# DDR3_ZET6_OLD.net
KiCad netlist of a schematic drawn in Altium Designer
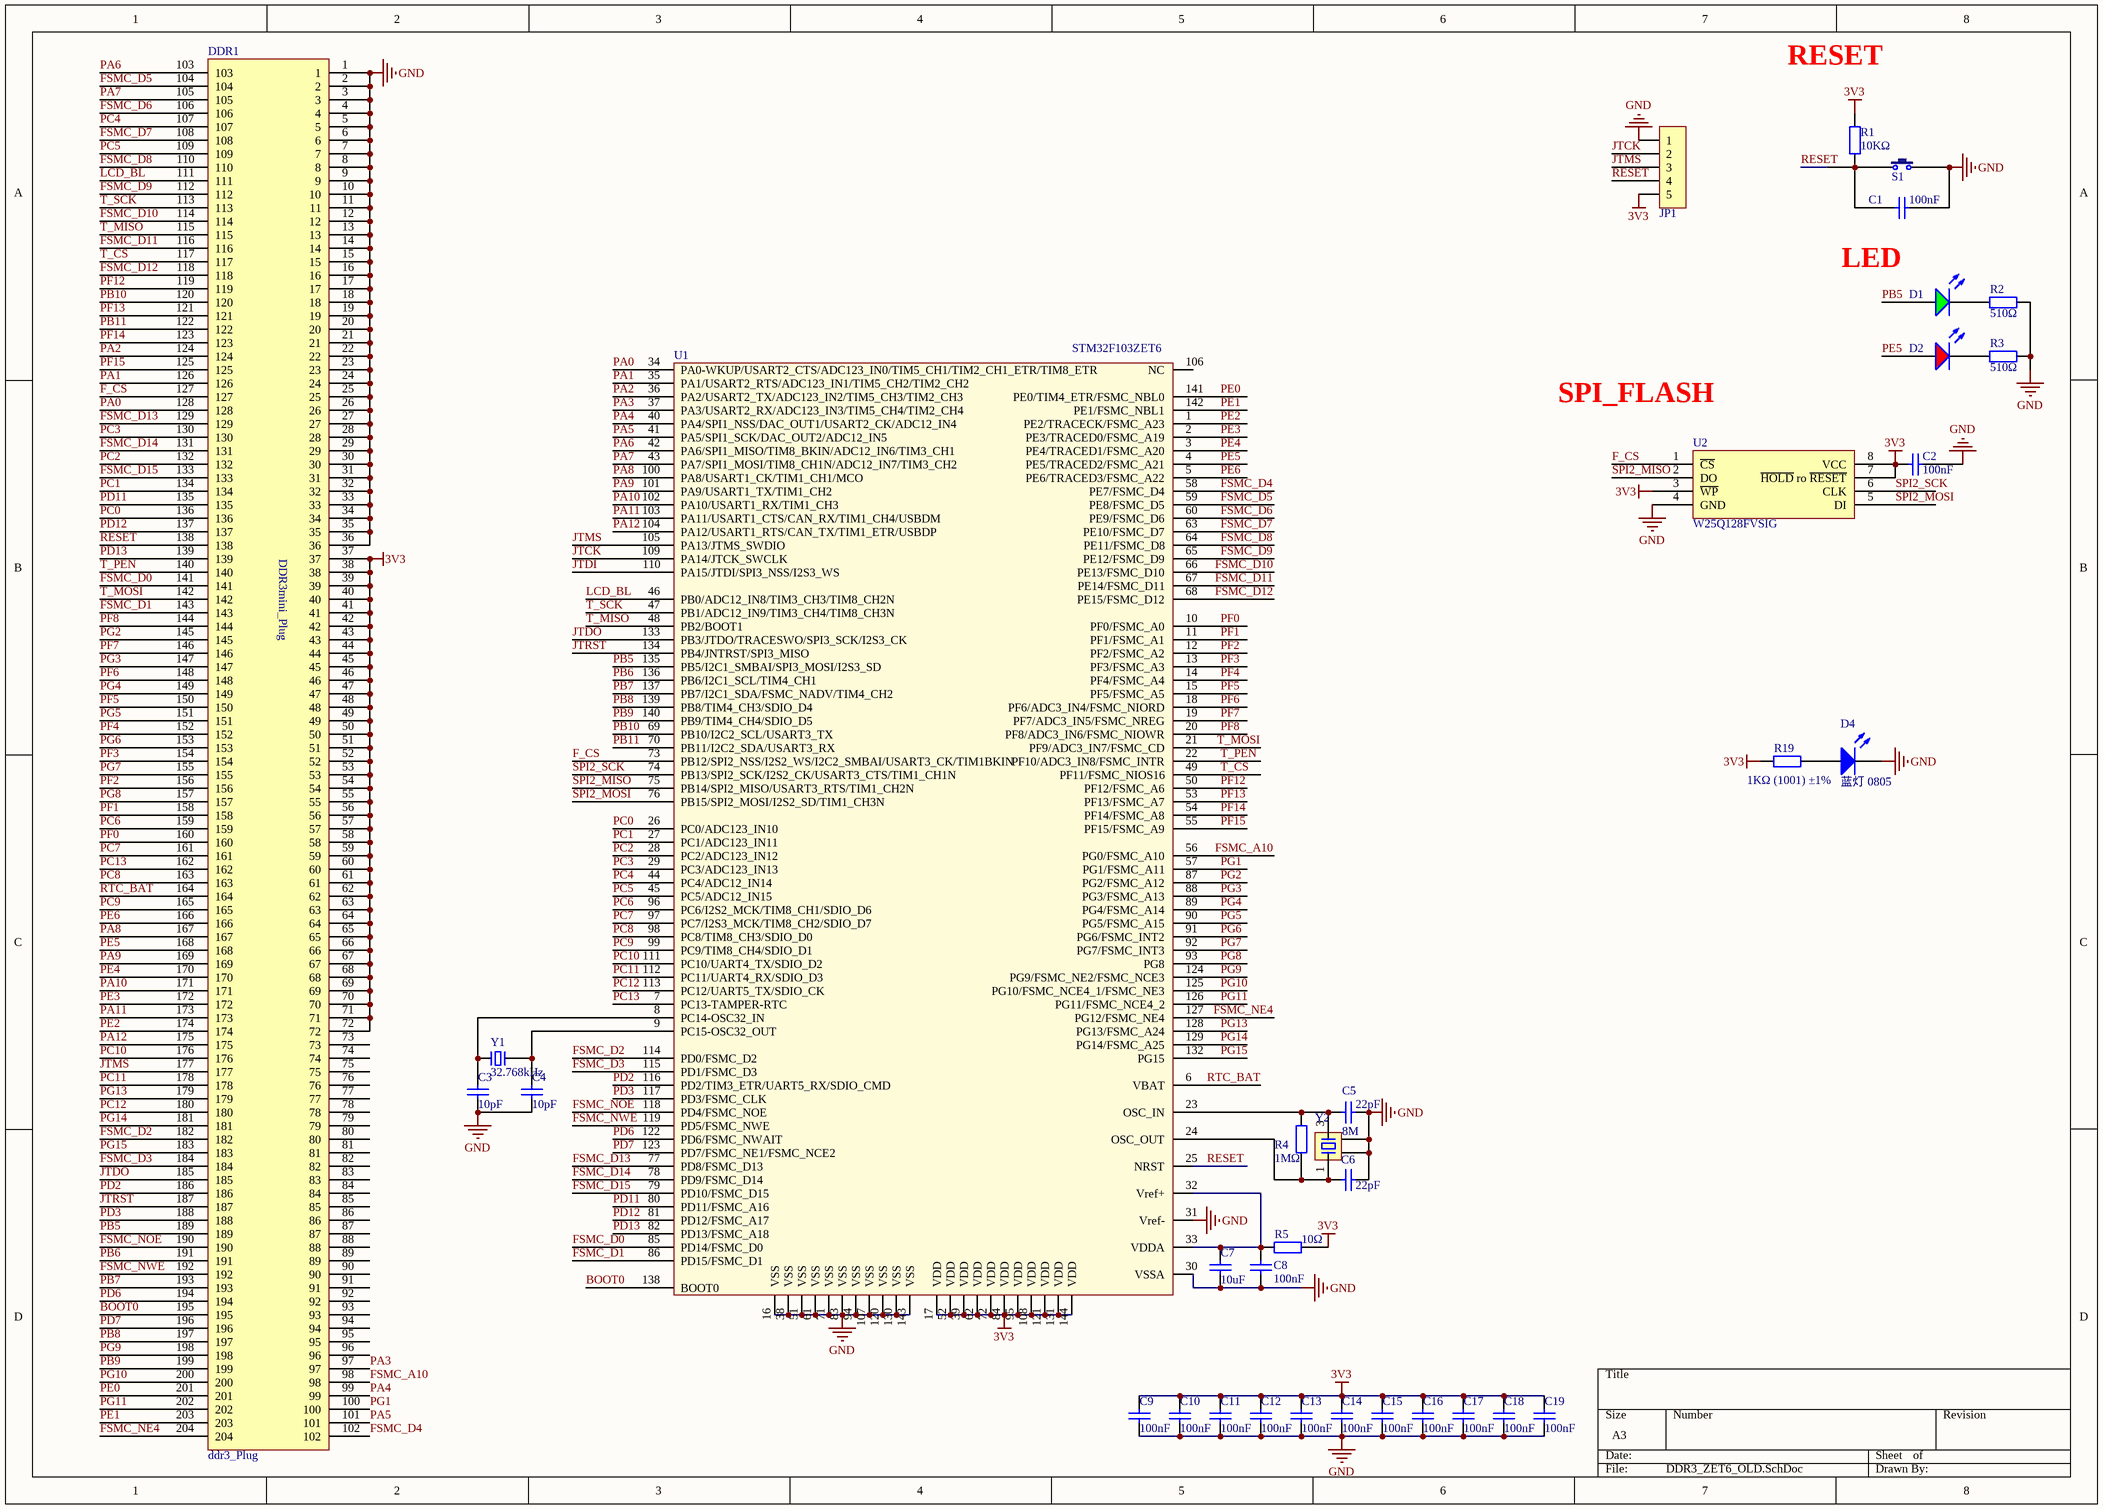
[diagram p0: DDR3_ZET6_OLD.SchDoc]

(export (version "E")
  (design (tool "Eeschema 10.0.6"))
  (components
    (comp (ref "C1")
      (value "100nF")
      (footprint "LC-0805_C")
      (description "贴片电容")
      (libsource (lib "Miscellaneous Devices LC") (part "0805 100nF(104) 10% 50V"))
    )
    (comp (ref "C2")
      (value "100nF")
      (footprint "LC-0805_C")
      (description "贴片电容")
      (libsource (lib "Miscellaneous Devices LC") (part "0805 100nF(104) 10% 50V"))
    )
    (comp (ref "C3")
      (value "10pF")
      (footprint "LC-0805_C")
      (description "贴片电容")
      (libsource (lib "Miscellaneous Devices LC") (part "0805 10pF (100) 5% 50V"))
    )
    (comp (ref "C4")
      (value "10pF")
      (footprint "LC-0805_C")
      (description "贴片电容")
      (libsource (lib "Miscellaneous Devices LC") (part "0805 10pF (100) 5% 50V"))
    )
    (comp (ref "C5")
      (value "22pF")
      (footprint "LC-0805_C")
      (description "贴片电容")
      (libsource (lib "Miscellaneous Devices LC") (part "0805 22pF (220) 5% 50V"))
    )
    (comp (ref "C6")
      (value "22pF")
      (footprint "LC-0805_C")
      (description "贴片电容")
      (libsource (lib "Miscellaneous Devices LC") (part "0805 22pF (220) 5% 50V"))
    )
    (comp (ref "C7")
      (value "10uF")
      (footprint "LC-0805_C")
      (description "贴片电容")
      (libsource (lib "Miscellaneous Devices LC") (part "0805 10uF (106) 10% 25V"))
    )
    (comp (ref "C8")
      (value "100nF")
      (footprint "LC-0805_C")
      (description "贴片电容")
      (libsource (lib "Miscellaneous Devices LC") (part "0805 100nF(104) 10% 50V"))
    )
    (comp (ref "C9")
      (value "100nF")
      (footprint "LC-0805_C")
      (description "贴片电容")
      (libsource (lib "Miscellaneous Devices LC") (part "0805 100nF(104) 10% 50V"))
    )
    (comp (ref "C10")
      (value "100nF")
      (footprint "LC-0805_C")
      (description "贴片电容")
      (libsource (lib "Miscellaneous Devices LC") (part "0805 100nF(104) 10% 50V"))
    )
    (comp (ref "C11")
      (value "100nF")
      (footprint "LC-0805_C")
      (description "贴片电容")
      (libsource (lib "Miscellaneous Devices LC") (part "0805 100nF(104) 10% 50V"))
    )
    (comp (ref "C12")
      (value "100nF")
      (footprint "LC-0805_C")
      (description "贴片电容")
      (libsource (lib "Miscellaneous Devices LC") (part "0805 100nF(104) 10% 50V"))
    )
    (comp (ref "C13")
      (value "100nF")
      (footprint "LC-0805_C")
      (description "贴片电容")
      (libsource (lib "Miscellaneous Devices LC") (part "0805 100nF(104) 10% 50V"))
    )
    (comp (ref "C14")
      (value "100nF")
      (footprint "LC-0805_C")
      (description "贴片电容")
      (libsource (lib "Miscellaneous Devices LC") (part "0805 100nF(104) 10% 50V"))
    )
    (comp (ref "C15")
      (value "100nF")
      (footprint "LC-0805_C")
      (description "贴片电容")
      (libsource (lib "Miscellaneous Devices LC") (part "0805 100nF(104) 10% 50V"))
    )
    (comp (ref "C16")
      (value "100nF")
      (footprint "LC-0805_C")
      (description "贴片电容")
      (libsource (lib "Miscellaneous Devices LC") (part "0805 100nF(104) 10% 50V"))
    )
    (comp (ref "C17")
      (value "100nF")
      (footprint "LC-0805_C")
      (description "贴片电容")
      (libsource (lib "Miscellaneous Devices LC") (part "0805 100nF(104) 10% 50V"))
    )
    (comp (ref "C18")
      (value "100nF")
      (footprint "LC-0805_C")
      (description "贴片电容")
      (libsource (lib "Miscellaneous Devices LC") (part "0805 100nF(104) 10% 50V"))
    )
    (comp (ref "C19")
      (value "100nF")
      (footprint "LC-0805_C")
      (description "贴片电容")
      (libsource (lib "Miscellaneous Devices LC") (part "0805 100nF(104) 10% 50V"))
    )
    (comp (ref "D1")
      (value "翠绿 0805")
      (footprint "LC-0805_LED_S1")
      (description "发光二极管")
      (libsource (lib "Miscellaneous Devices LC") (part "0805 翠绿"))
    )
    (comp (ref "D2")
      (value "红灯 0805")
      (footprint "LC-0805_LED_S1")
      (description "发光二极管")
      (libsource (lib "Miscellaneous Devices LC") (part "0805 红灯"))
    )
    (comp (ref "D4")
      (value "蓝灯 0805")
      (footprint "LC-0805_LED_S1")
      (description "发光二极管")
      (libsource (lib "Miscellaneous Devices LC") (part "0805 蓝灯"))
    )
    (comp (ref "DDR1")
      (value "ddr3_Plug")
      (footprint "DDR3_PLUG_LTE")
      (libsource (lib "my_lib") (part "ddr3_Plug"))
    )
    (comp (ref "JP1")
      (value "HDR-1X5")
      (footprint "HDR-1X5")
      (description "5P接插件")
      (fields (field (name "版权归属") "黎明电子style"))
      (libsource (lib "接插件") (part "Header 5"))
    )
    (comp (ref "R1")
      (value "10KΩ")
      (footprint "LC-0805_R")
      (description "贴片电阻")
      (libsource (lib "Miscellaneous Devices LC") (part "0805 10KΩ (1002) 1%"))
    )
    (comp (ref "R2")
      (value "510Ω")
      (footprint "LC-0805_R")
      (description "贴片电阻")
      (libsource (lib "Miscellaneous Devices LC") (part "0805 510Ω (5100) 1%"))
    )
    (comp (ref "R3")
      (value "510Ω")
      (footprint "LC-0805_R")
      (description "贴片电阻")
      (libsource (lib "Miscellaneous Devices LC") (part "0805 510Ω (5100) 1%"))
    )
    (comp (ref "R4")
      (value "1MΩ")
      (footprint "LC-0805_R")
      (description "贴片电阻")
      (libsource (lib "Miscellaneous Devices LC") (part "0805 1MΩ (1004) 1%"))
    )
    (comp (ref "R5")
      (value "10Ω")
      (footprint "LC-0805_R")
      (description "贴片电阻")
      (libsource (lib "Miscellaneous Devices LC") (part "0805 10Ω (10R0) 1%"))
    )
    (comp (ref "R19")
      (value "1KΩ (1001) ±1%")
      (footprint "LC-0805_R")
      (description "贴片电阻")
      (libsource (lib "Miscellaneous Devices LC") (part "0805 1KΩ (1001) 1%"))
    )
    (comp (ref "S1")
      (value "RESET")
      (footprint "TSW SMD-3*6*2.5")
      (description "3x6轻触开关")
      (fields (field (name "版权归属") "黎明电子style"))
      (libsource (lib "按键-开关") (part "TSW 3x6"))
    )
    (comp (ref "U1")
      (value "STM32F103ZET6")
      (footprint "LC-LQFP-144_20x20x05P")
      (libsource (lib "WarShip V3 STM32103封装库") (part "STM32F103ZET6"))
    )
    (comp (ref "U2")
      (value "W25Q128FVSIG")
      (footprint "LC-SOIC-8_208mil")
      (description "Flash ROM")
      (libsource (lib "Miscellaneous Devices LC") (part "W25Q128FVSIG"))
    )
    (comp (ref "Y1")
      (value "32.768kHz")
      (footprint "XTAL-3215")
      (description "2脚晶振")
      (fields (field (name "版权归属") "黎明电子style"))
      (libsource (lib "保险丝-晶振") (part "XTAL-2"))
    )
    (comp (ref "Y2")
      (value "8M")
      (footprint "XTAL-3225")
      (description "4脚晶振")
      (fields (field (name "版权归属") "黎明电子style"))
      (libsource (lib "保险丝-晶振") (part "XTAL-4"))
    )
  )
  (nets
    (net (code "1") (name "/BOOT0") (class "Default")
      (node (ref "DDR1") (pin "195") (pinfunction "195_195") (pintype "passive"))
      (node (ref "U1") (pin "138") (pinfunction "BOOT0_138") (pintype "passive"))
    )
    (net (code "2") (name "/FSMC_A10") (class "Default")
      (node (ref "DDR1") (pin "98") (pinfunction "98_98") (pintype "passive"))
      (node (ref "U1") (pin "56") (pinfunction "PG0/FSMC_A10_56") (pintype "passive"))
    )
    (net (code "3") (name "/FSMC_D0") (class "Default")
      (node (ref "DDR1") (pin "141") (pinfunction "141_141") (pintype "passive"))
      (node (ref "U1") (pin "85") (pinfunction "PD14/FSMC_D0_85") (pintype "passive"))
    )
    (net (code "4") (name "/FSMC_D1") (class "Default")
      (node (ref "DDR1") (pin "143") (pinfunction "143_143") (pintype "passive"))
      (node (ref "U1") (pin "86") (pinfunction "PD15/FSMC_D1_86") (pintype "passive"))
    )
    (net (code "5") (name "/FSMC_D2") (class "Default")
      (node (ref "DDR1") (pin "182") (pinfunction "182_182") (pintype "passive"))
      (node (ref "U1") (pin "114") (pinfunction "PD0/FSMC_D2_114") (pintype "passive"))
    )
    (net (code "6") (name "/FSMC_D3") (class "Default")
      (node (ref "DDR1") (pin "184") (pinfunction "184_184") (pintype "passive"))
      (node (ref "U1") (pin "115") (pinfunction "PD1/FSMC_D3_115") (pintype "passive"))
    )
    (net (code "7") (name "/FSMC_D4") (class "Default")
      (node (ref "DDR1") (pin "102") (pinfunction "102_102") (pintype "passive"))
      (node (ref "U1") (pin "58") (pinfunction "PE7/FSMC_D4_58") (pintype "passive"))
    )
    (net (code "8") (name "/FSMC_D5") (class "Default")
      (node (ref "DDR1") (pin "104") (pinfunction "104_104") (pintype "passive"))
      (node (ref "U1") (pin "59") (pinfunction "PE8/FSMC_D5_59") (pintype "passive"))
    )
    (net (code "9") (name "/FSMC_D6") (class "Default")
      (node (ref "DDR1") (pin "106") (pinfunction "106_106") (pintype "passive"))
      (node (ref "U1") (pin "60") (pinfunction "PE9/FSMC_D6_60") (pintype "passive"))
    )
    (net (code "10") (name "/FSMC_D7") (class "Default")
      (node (ref "DDR1") (pin "108") (pinfunction "108_108") (pintype "passive"))
      (node (ref "U1") (pin "63") (pinfunction "PE10/FSMC_D7_63") (pintype "passive"))
    )
    (net (code "11") (name "/FSMC_D8") (class "Default")
      (node (ref "DDR1") (pin "110") (pinfunction "110_110") (pintype "passive"))
      (node (ref "U1") (pin "64") (pinfunction "PE11/FSMC_D8_64") (pintype "passive"))
    )
    (net (code "12") (name "/FSMC_D9") (class "Default")
      (node (ref "DDR1") (pin "112") (pinfunction "112_112") (pintype "passive"))
      (node (ref "U1") (pin "65") (pinfunction "PE12/FSMC_D9_65") (pintype "passive"))
    )
    (net (code "13") (name "/FSMC_D10") (class "Default")
      (node (ref "DDR1") (pin "114") (pinfunction "114_114") (pintype "passive"))
      (node (ref "U1") (pin "66") (pinfunction "PE13/FSMC_D10_66") (pintype "passive"))
    )
    (net (code "14") (name "/FSMC_D11") (class "Default")
      (node (ref "DDR1") (pin "116") (pinfunction "116_116") (pintype "passive"))
      (node (ref "U1") (pin "67") (pinfunction "PE14/FSMC_D11_67") (pintype "passive"))
    )
    (net (code "15") (name "/FSMC_D12") (class "Default")
      (node (ref "DDR1") (pin "118") (pinfunction "118_118") (pintype "passive"))
      (node (ref "U1") (pin "68") (pinfunction "PE15/FSMC_D12_68") (pintype "passive"))
    )
    (net (code "16") (name "/FSMC_D13") (class "Default")
      (node (ref "DDR1") (pin "129") (pinfunction "129_129") (pintype "passive"))
      (node (ref "U1") (pin "77") (pinfunction "PD8/FSMC_D13_77") (pintype "passive"))
    )
    (net (code "17") (name "/FSMC_D14") (class "Default")
      (node (ref "DDR1") (pin "131") (pinfunction "131_131") (pintype "passive"))
      (node (ref "U1") (pin "78") (pinfunction "PD9/FSMC_D14_78") (pintype "passive"))
    )
    (net (code "18") (name "/FSMC_D15") (class "Default")
      (node (ref "DDR1") (pin "133") (pinfunction "133_133") (pintype "passive"))
      (node (ref "U1") (pin "79") (pinfunction "PD10/FSMC_D15_79") (pintype "passive"))
    )
    (net (code "19") (name "/FSMC_NE4") (class "Default")
      (node (ref "DDR1") (pin "204") (pinfunction "204_204") (pintype "passive"))
      (node (ref "U1") (pin "127") (pinfunction "PG12/FSMC_NE4_127") (pintype "passive"))
    )
    (net (code "20") (name "/FSMC_NOE") (class "Default")
      (node (ref "DDR1") (pin "190") (pinfunction "190_190") (pintype "passive"))
      (node (ref "U1") (pin "118") (pinfunction "PD4/FSMC_NOE_118") (pintype "passive"))
    )
    (net (code "21") (name "/FSMC_NWE") (class "Default")
      (node (ref "DDR1") (pin "192") (pinfunction "192_192") (pintype "passive"))
      (node (ref "U1") (pin "119") (pinfunction "PD5/FSMC_NWE_119") (pintype "passive"))
    )
    (net (code "22") (name "/F_CS") (class "Default")
      (node (ref "DDR1") (pin "127") (pinfunction "127_127") (pintype "passive"))
      (node (ref "U1") (pin "73") (pinfunction "PB12/SPI2_NSS/I2S2_WS/I2C2_SMBAI/USART3_CK/TIM1BKIN_73") (pintype "passive"))
      (node (ref "U2") (pin "1") (pinfunction "~{CS}_1") (pintype "passive"))
    )
    (net (code "23") (name "/JTCK") (class "Default")
      (node (ref "JP1") (pin "2") (pinfunction "2_2") (pintype "passive"))
      (node (ref "U1") (pin "109") (pinfunction "PA14/JTCK_SWCLK_109") (pintype "passive"))
    )
    (net (code "24") (name "/JTDI") (class "Default")
      (node (ref "U1") (pin "110") (pinfunction "PA15/JTDI/SPI3_NSS/I2S3_WS_110") (pintype "passive"))
    )
    (net (code "25") (name "/JTDO") (class "Default")
      (node (ref "DDR1") (pin "185") (pinfunction "185_185") (pintype "passive"))
      (node (ref "U1") (pin "133") (pinfunction "PB3/JTDO/TRACESWO/SPI3_SCK/I2S3_CK_133") (pintype "passive"))
    )
    (net (code "26") (name "/JTMS") (class "Default")
      (node (ref "DDR1") (pin "177") (pinfunction "177_177") (pintype "passive"))
      (node (ref "JP1") (pin "3") (pinfunction "3_3") (pintype "passive"))
      (node (ref "U1") (pin "105") (pinfunction "PA13/JTMS_SWDIO_105") (pintype "passive"))
    )
    (net (code "27") (name "/JTRST") (class "Default")
      (node (ref "DDR1") (pin "187") (pinfunction "187_187") (pintype "passive"))
      (node (ref "U1") (pin "134") (pinfunction "PB4/JNTRST/SPI3_MISO_134") (pintype "passive"))
    )
    (net (code "28") (name "/LCD_BL") (class "Default")
      (node (ref "DDR1") (pin "111") (pinfunction "111_111") (pintype "passive"))
      (node (ref "U1") (pin "46") (pinfunction "PB0/ADC12_IN8/TIM3_CH3/TIM8_CH2N_46") (pintype "passive"))
    )
    (net (code "29") (name "/PA0") (class "Default")
      (node (ref "DDR1") (pin "128") (pinfunction "128_128") (pintype "passive"))
      (node (ref "U1") (pin "34") (pinfunction "PA0-WKUP/USART2_CTS/ADC123_IN0/TIM5_CH1/TIM2_CH1_ETR/TIM8_ETR_34") (pintype "passive"))
    )
    (net (code "30") (name "/PA1") (class "Default")
      (node (ref "DDR1") (pin "126") (pinfunction "126_126") (pintype "passive"))
      (node (ref "U1") (pin "35") (pinfunction "PA1/USART2_RTS/ADC123_IN1/TIM5_CH2/TIM2_CH2_35") (pintype "passive"))
    )
    (net (code "31") (name "/PA2") (class "Default")
      (node (ref "DDR1") (pin "124") (pinfunction "124_124") (pintype "passive"))
      (node (ref "U1") (pin "36") (pinfunction "PA2/USART2_TX/ADC123_IN2/TIM5_CH3/TIM2_CH3_36") (pintype "passive"))
    )
    (net (code "32") (name "/PA3") (class "Default")
      (node (ref "DDR1") (pin "97") (pinfunction "97_97") (pintype "passive"))
      (node (ref "U1") (pin "37") (pinfunction "PA3/USART2_RX/ADC123_IN3/TIM5_CH4/TIM2_CH4_37") (pintype "passive"))
    )
    (net (code "33") (name "/PA4") (class "Default")
      (node (ref "DDR1") (pin "99") (pinfunction "99_99") (pintype "passive"))
      (node (ref "U1") (pin "40") (pinfunction "PA4/SPI1_NSS/DAC_OUT1/USART2_CK/ADC12_IN4_40") (pintype "passive"))
    )
    (net (code "34") (name "/PA5") (class "Default")
      (node (ref "DDR1") (pin "101") (pinfunction "101_101") (pintype "passive"))
      (node (ref "U1") (pin "41") (pinfunction "PA5/SPI1_SCK/DAC_OUT2/ADC12_IN5_41") (pintype "passive"))
    )
    (net (code "35") (name "/PA6") (class "Default")
      (node (ref "DDR1") (pin "103") (pinfunction "103_103") (pintype "passive"))
      (node (ref "U1") (pin "42") (pinfunction "PA6/SPI1_MISO/TIM8_BKIN/ADC12_IN6/TIM3_CH1_42") (pintype "passive"))
    )
    (net (code "36") (name "/PA7") (class "Default")
      (node (ref "DDR1") (pin "105") (pinfunction "105_105") (pintype "passive"))
      (node (ref "U1") (pin "43") (pinfunction "PA7/SPI1_MOSI/TIM8_CH1N/ADC12_IN7/TIM3_CH2_43") (pintype "passive"))
    )
    (net (code "37") (name "/PA8") (class "Default")
      (node (ref "DDR1") (pin "167") (pinfunction "167_167") (pintype "passive"))
      (node (ref "U1") (pin "100") (pinfunction "PA8/USART1_CK/TIM1_CH1/MCO_100") (pintype "passive"))
    )
    (net (code "38") (name "/PA9") (class "Default")
      (node (ref "DDR1") (pin "169") (pinfunction "169_169") (pintype "passive"))
      (node (ref "U1") (pin "101") (pinfunction "PA9/USART1_TX/TIM1_CH2_101") (pintype "passive"))
    )
    (net (code "39") (name "/PA10") (class "Default")
      (node (ref "DDR1") (pin "171") (pinfunction "171_171") (pintype "passive"))
      (node (ref "U1") (pin "102") (pinfunction "PA10/USART1_RX/TIM1_CH3_102") (pintype "passive"))
    )
    (net (code "40") (name "/PA11") (class "Default")
      (node (ref "DDR1") (pin "173") (pinfunction "173_173") (pintype "passive"))
      (node (ref "U1") (pin "103") (pinfunction "PA11/USART1_CTS/CAN_RX/TIM1_CH4/USBDM_103") (pintype "passive"))
    )
    (net (code "41") (name "/PA12") (class "Default")
      (node (ref "DDR1") (pin "175") (pinfunction "175_175") (pintype "passive"))
      (node (ref "U1") (pin "104") (pinfunction "PA12/USART1_RTS/CAN_TX/TIM1_ETR/USBDP_104") (pintype "passive"))
    )
    (net (code "42") (name "/PB5") (class "Default")
      (node (ref "D1") (pin "A") (pinfunction "A_A") (pintype "passive"))
      (node (ref "DDR1") (pin "189") (pinfunction "189_189") (pintype "passive"))
      (node (ref "U1") (pin "135") (pinfunction "PB5/I2C1_SMBAI/SPI3_MOSI/I2S3_SD_135") (pintype "passive"))
    )
    (net (code "43") (name "/PB6") (class "Default")
      (node (ref "DDR1") (pin "191") (pinfunction "191_191") (pintype "passive"))
      (node (ref "U1") (pin "136") (pinfunction "PB6/I2C1_SCL/TIM4_CH1_136") (pintype "passive"))
    )
    (net (code "44") (name "/PB7") (class "Default")
      (node (ref "DDR1") (pin "193") (pinfunction "193_193") (pintype "passive"))
      (node (ref "U1") (pin "137") (pinfunction "PB7/I2C1_SDA/FSMC_NADV/TIM4_CH2_137") (pintype "passive"))
    )
    (net (code "45") (name "/PB8") (class "Default")
      (node (ref "DDR1") (pin "197") (pinfunction "197_197") (pintype "passive"))
      (node (ref "U1") (pin "139") (pinfunction "PB8/TIM4_CH3/SDIO_D4_139") (pintype "passive"))
    )
    (net (code "46") (name "/PB9") (class "Default")
      (node (ref "DDR1") (pin "199") (pinfunction "199_199") (pintype "passive"))
      (node (ref "U1") (pin "140") (pinfunction "PB9/TIM4_CH4/SDIO_D5_140") (pintype "passive"))
    )
    (net (code "47") (name "/PB10") (class "Default")
      (node (ref "DDR1") (pin "120") (pinfunction "120_120") (pintype "passive"))
      (node (ref "U1") (pin "69") (pinfunction "PB10/I2C2_SCL/USART3_TX_69") (pintype "passive"))
    )
    (net (code "48") (name "/PB11") (class "Default")
      (node (ref "DDR1") (pin "122") (pinfunction "122_122") (pintype "passive"))
      (node (ref "U1") (pin "70") (pinfunction "PB11/I2C2_SDA/USART3_RX_70") (pintype "passive"))
    )
    (net (code "49") (name "/PC0") (class "Default")
      (node (ref "DDR1") (pin "136") (pinfunction "136_136") (pintype "passive"))
      (node (ref "U1") (pin "26") (pinfunction "PC0/ADC123_IN10_26") (pintype "passive"))
    )
    (net (code "50") (name "/PC1") (class "Default")
      (node (ref "DDR1") (pin "134") (pinfunction "134_134") (pintype "passive"))
      (node (ref "U1") (pin "27") (pinfunction "PC1/ADC123_IN11_27") (pintype "passive"))
    )
    (net (code "51") (name "/PC2") (class "Default")
      (node (ref "DDR1") (pin "132") (pinfunction "132_132") (pintype "passive"))
      (node (ref "U1") (pin "28") (pinfunction "PC2/ADC123_IN12_28") (pintype "passive"))
    )
    (net (code "52") (name "/PC3") (class "Default")
      (node (ref "DDR1") (pin "130") (pinfunction "130_130") (pintype "passive"))
      (node (ref "U1") (pin "29") (pinfunction "PC3/ADC123_IN13_29") (pintype "passive"))
    )
    (net (code "53") (name "/PC4") (class "Default")
      (node (ref "DDR1") (pin "107") (pinfunction "107_107") (pintype "passive"))
      (node (ref "U1") (pin "44") (pinfunction "PC4/ADC12_IN14_44") (pintype "passive"))
    )
    (net (code "54") (name "/PC5") (class "Default")
      (node (ref "DDR1") (pin "109") (pinfunction "109_109") (pintype "passive"))
      (node (ref "U1") (pin "45") (pinfunction "PC5/ADC12_IN15_45") (pintype "passive"))
    )
    (net (code "55") (name "/PC6") (class "Default")
      (node (ref "DDR1") (pin "159") (pinfunction "159_159") (pintype "passive"))
      (node (ref "U1") (pin "96") (pinfunction "PC6/I2S2_MCK/TIM8_CH1/SDIO_D6_96") (pintype "passive"))
    )
    (net (code "56") (name "/PC7") (class "Default")
      (node (ref "DDR1") (pin "161") (pinfunction "161_161") (pintype "passive"))
      (node (ref "U1") (pin "97") (pinfunction "PC7/I2S3_MCK/TIM8_CH2/SDIO_D7_97") (pintype "passive"))
    )
    (net (code "57") (name "/PC8") (class "Default")
      (node (ref "DDR1") (pin "163") (pinfunction "163_163") (pintype "passive"))
      (node (ref "U1") (pin "98") (pinfunction "PC8/TIM8_CH3/SDIO_D0_98") (pintype "passive"))
    )
    (net (code "58") (name "/PC9") (class "Default")
      (node (ref "DDR1") (pin "165") (pinfunction "165_165") (pintype "passive"))
      (node (ref "U1") (pin "99") (pinfunction "PC9/TIM8_CH4/SDIO_D1_99") (pintype "passive"))
    )
    (net (code "59") (name "/PC10") (class "Default")
      (node (ref "DDR1") (pin "176") (pinfunction "176_176") (pintype "passive"))
      (node (ref "U1") (pin "111") (pinfunction "PC10/UART4_TX/SDIO_D2_111") (pintype "passive"))
    )
    (net (code "60") (name "/PC11") (class "Default")
      (node (ref "DDR1") (pin "178") (pinfunction "178_178") (pintype "passive"))
      (node (ref "U1") (pin "112") (pinfunction "PC11/UART4_RX/SDIO_D3_112") (pintype "passive"))
    )
    (net (code "61") (name "/PC12") (class "Default")
      (node (ref "DDR1") (pin "180") (pinfunction "180_180") (pintype "passive"))
      (node (ref "U1") (pin "113") (pinfunction "PC12/UART5_TX/SDIO_CK_113") (pintype "passive"))
    )
    (net (code "62") (name "/PC13") (class "Default")
      (node (ref "DDR1") (pin "162") (pinfunction "162_162") (pintype "passive"))
      (node (ref "U1") (pin "7") (pinfunction "PC13-TAMPER-RTC_7") (pintype "passive"))
    )
    (net (code "63") (name "/PD2") (class "Default")
      (node (ref "DDR1") (pin "186") (pinfunction "186_186") (pintype "passive"))
      (node (ref "U1") (pin "116") (pinfunction "PD2/TIM3_ETR/UART5_RX/SDIO_CMD_116") (pintype "passive"))
    )
    (net (code "64") (name "/PD3") (class "Default")
      (node (ref "DDR1") (pin "188") (pinfunction "188_188") (pintype "passive"))
      (node (ref "U1") (pin "117") (pinfunction "PD3/FSMC_CLK_117") (pintype "passive"))
    )
    (net (code "65") (name "/PD6") (class "Default")
      (node (ref "DDR1") (pin "194") (pinfunction "194_194") (pintype "passive"))
      (node (ref "U1") (pin "122") (pinfunction "PD6/FSMC_NWAIT_122") (pintype "passive"))
    )
    (net (code "66") (name "/PD7") (class "Default")
      (node (ref "DDR1") (pin "196") (pinfunction "196_196") (pintype "passive"))
      (node (ref "U1") (pin "123") (pinfunction "PD7/FSMC_NE1/FSMC_NCE2_123") (pintype "passive"))
    )
    (net (code "67") (name "/PD11") (class "Default")
      (node (ref "DDR1") (pin "135") (pinfunction "135_135") (pintype "passive"))
      (node (ref "U1") (pin "80") (pinfunction "PD11/FSMC_A16_80") (pintype "passive"))
    )
    (net (code "68") (name "/PD12") (class "Default")
      (node (ref "DDR1") (pin "137") (pinfunction "137_137") (pintype "passive"))
      (node (ref "U1") (pin "81") (pinfunction "PD12/FSMC_A17_81") (pintype "passive"))
    )
    (net (code "69") (name "/PD13") (class "Default")
      (node (ref "DDR1") (pin "139") (pinfunction "139_139") (pintype "passive"))
      (node (ref "U1") (pin "82") (pinfunction "PD13/FSMC_A18_82") (pintype "passive"))
    )
    (net (code "70") (name "/PE0") (class "Default")
      (node (ref "DDR1") (pin "201") (pinfunction "201_201") (pintype "passive"))
      (node (ref "U1") (pin "141") (pinfunction "PE0/TIM4_ETR/FSMC_NBL0_141") (pintype "passive"))
    )
    (net (code "71") (name "/PE1") (class "Default")
      (node (ref "DDR1") (pin "203") (pinfunction "203_203") (pintype "passive"))
      (node (ref "U1") (pin "142") (pinfunction "PE1/FSMC_NBL1_142") (pintype "passive"))
    )
    (net (code "72") (name "/PE2") (class "Default")
      (node (ref "DDR1") (pin "174") (pinfunction "174_174") (pintype "passive"))
      (node (ref "U1") (pin "1") (pinfunction "PE2/TRACECK/FSMC_A23_1") (pintype "passive"))
    )
    (net (code "73") (name "/PE3") (class "Default")
      (node (ref "DDR1") (pin "172") (pinfunction "172_172") (pintype "passive"))
      (node (ref "U1") (pin "2") (pinfunction "PE3/TRACED0/FSMC_A19_2") (pintype "passive"))
    )
    (net (code "74") (name "/PE4") (class "Default")
      (node (ref "DDR1") (pin "170") (pinfunction "170_170") (pintype "passive"))
      (node (ref "U1") (pin "3") (pinfunction "PE4/TRACED1/FSMC_A20_3") (pintype "passive"))
    )
    (net (code "75") (name "/PE5") (class "Default")
      (node (ref "D2") (pin "A") (pinfunction "A_A") (pintype "passive"))
      (node (ref "DDR1") (pin "168") (pinfunction "168_168") (pintype "passive"))
      (node (ref "U1") (pin "4") (pinfunction "PE5/TRACED2/FSMC_A21_4") (pintype "passive"))
    )
    (net (code "76") (name "/PE6") (class "Default")
      (node (ref "DDR1") (pin "166") (pinfunction "166_166") (pintype "passive"))
      (node (ref "U1") (pin "5") (pinfunction "PE6/TRACED3/FSMC_A22_5") (pintype "passive"))
    )
    (net (code "77") (name "/PF0") (class "Default")
      (node (ref "DDR1") (pin "160") (pinfunction "160_160") (pintype "passive"))
      (node (ref "U1") (pin "10") (pinfunction "PF0/FSMC_A0_10") (pintype "passive"))
    )
    (net (code "78") (name "/PF1") (class "Default")
      (node (ref "DDR1") (pin "158") (pinfunction "158_158") (pintype "passive"))
      (node (ref "U1") (pin "11") (pinfunction "PF1/FSMC_A1_11") (pintype "passive"))
    )
    (net (code "79") (name "/PF2") (class "Default")
      (node (ref "DDR1") (pin "156") (pinfunction "156_156") (pintype "passive"))
      (node (ref "U1") (pin "12") (pinfunction "PF2/FSMC_A2_12") (pintype "passive"))
    )
    (net (code "80") (name "/PF3") (class "Default")
      (node (ref "DDR1") (pin "154") (pinfunction "154_154") (pintype "passive"))
      (node (ref "U1") (pin "13") (pinfunction "PF3/FSMC_A3_13") (pintype "passive"))
    )
    (net (code "81") (name "/PF4") (class "Default")
      (node (ref "DDR1") (pin "152") (pinfunction "152_152") (pintype "passive"))
      (node (ref "U1") (pin "14") (pinfunction "PF4/FSMC_A4_14") (pintype "passive"))
    )
    (net (code "82") (name "/PF5") (class "Default")
      (node (ref "DDR1") (pin "150") (pinfunction "150_150") (pintype "passive"))
      (node (ref "U1") (pin "15") (pinfunction "PF5/FSMC_A5_15") (pintype "passive"))
    )
    (net (code "83") (name "/PF6") (class "Default")
      (node (ref "DDR1") (pin "148") (pinfunction "148_148") (pintype "passive"))
      (node (ref "U1") (pin "18") (pinfunction "PF6/ADC3_IN4/FSMC_NIORD_18") (pintype "passive"))
    )
    (net (code "84") (name "/PF7") (class "Default")
      (node (ref "DDR1") (pin "146") (pinfunction "146_146") (pintype "passive"))
      (node (ref "U1") (pin "19") (pinfunction "PF7/ADC3_IN5/FSMC_NREG_19") (pintype "passive"))
    )
    (net (code "85") (name "/PF8") (class "Default")
      (node (ref "DDR1") (pin "144") (pinfunction "144_144") (pintype "passive"))
      (node (ref "U1") (pin "20") (pinfunction "PF8/ADC3_IN6/FSMC_NIOWR_20") (pintype "passive"))
    )
    (net (code "86") (name "/PF12") (class "Default")
      (node (ref "DDR1") (pin "119") (pinfunction "119_119") (pintype "passive"))
      (node (ref "U1") (pin "50") (pinfunction "PF12/FSMC_A6_50") (pintype "passive"))
    )
    (net (code "87") (name "/PF13") (class "Default")
      (node (ref "DDR1") (pin "121") (pinfunction "121_121") (pintype "passive"))
      (node (ref "U1") (pin "53") (pinfunction "PF13/FSMC_A7_53") (pintype "passive"))
    )
    (net (code "88") (name "/PF14") (class "Default")
      (node (ref "DDR1") (pin "123") (pinfunction "123_123") (pintype "passive"))
      (node (ref "U1") (pin "54") (pinfunction "PF14/FSMC_A8_54") (pintype "passive"))
    )
    (net (code "89") (name "/PF15") (class "Default")
      (node (ref "DDR1") (pin "125") (pinfunction "125_125") (pintype "passive"))
      (node (ref "U1") (pin "55") (pinfunction "PF15/FSMC_A9_55") (pintype "passive"))
    )
    (net (code "90") (name "/PG1") (class "Default")
      (node (ref "DDR1") (pin "100") (pinfunction "100_100") (pintype "passive"))
      (node (ref "U1") (pin "57") (pinfunction "PG1/FSMC_A11_57") (pintype "passive"))
    )
    (net (code "91") (name "/PG2") (class "Default")
      (node (ref "DDR1") (pin "145") (pinfunction "145_145") (pintype "passive"))
      (node (ref "U1") (pin "87") (pinfunction "PG2/FSMC_A12_87") (pintype "passive"))
    )
    (net (code "92") (name "/PG3") (class "Default")
      (node (ref "DDR1") (pin "147") (pinfunction "147_147") (pintype "passive"))
      (node (ref "U1") (pin "88") (pinfunction "PG3/FSMC_A13_88") (pintype "passive"))
    )
    (net (code "93") (name "/PG4") (class "Default")
      (node (ref "DDR1") (pin "149") (pinfunction "149_149") (pintype "passive"))
      (node (ref "U1") (pin "89") (pinfunction "PG4/FSMC_A14_89") (pintype "passive"))
    )
    (net (code "94") (name "/PG5") (class "Default")
      (node (ref "DDR1") (pin "151") (pinfunction "151_151") (pintype "passive"))
      (node (ref "U1") (pin "90") (pinfunction "PG5/FSMC_A15_90") (pintype "passive"))
    )
    (net (code "95") (name "/PG6") (class "Default")
      (node (ref "DDR1") (pin "153") (pinfunction "153_153") (pintype "passive"))
      (node (ref "U1") (pin "91") (pinfunction "PG6/FSMC_INT2_91") (pintype "passive"))
    )
    (net (code "96") (name "/PG7") (class "Default")
      (node (ref "DDR1") (pin "155") (pinfunction "155_155") (pintype "passive"))
      (node (ref "U1") (pin "92") (pinfunction "PG7/FSMC_INT3_92") (pintype "passive"))
    )
    (net (code "97") (name "/PG8") (class "Default")
      (node (ref "DDR1") (pin "157") (pinfunction "157_157") (pintype "passive"))
      (node (ref "U1") (pin "93") (pinfunction "PG8_93") (pintype "passive"))
    )
    (net (code "98") (name "/PG9") (class "Default")
      (node (ref "DDR1") (pin "198") (pinfunction "198_198") (pintype "passive"))
      (node (ref "U1") (pin "124") (pinfunction "PG9/FSMC_NE2/FSMC_NCE3_124") (pintype "passive"))
    )
    (net (code "99") (name "/PG10") (class "Default")
      (node (ref "DDR1") (pin "200") (pinfunction "200_200") (pintype "passive"))
      (node (ref "U1") (pin "125") (pinfunction "PG10/FSMC_NCE4_1/FSMC_NE3_125") (pintype "passive"))
    )
    (net (code "100") (name "/PG11") (class "Default")
      (node (ref "DDR1") (pin "202") (pinfunction "202_202") (pintype "passive"))
      (node (ref "U1") (pin "126") (pinfunction "PG11/FSMC_NCE4_2_126") (pintype "passive"))
    )
    (net (code "101") (name "/PG13") (class "Default")
      (node (ref "DDR1") (pin "179") (pinfunction "179_179") (pintype "passive"))
      (node (ref "U1") (pin "128") (pinfunction "PG13/FSMC_A24_128") (pintype "passive"))
    )
    (net (code "102") (name "/PG14") (class "Default")
      (node (ref "DDR1") (pin "181") (pinfunction "181_181") (pintype "passive"))
      (node (ref "U1") (pin "129") (pinfunction "PG14/FSMC_A25_129") (pintype "passive"))
    )
    (net (code "103") (name "/PG15") (class "Default")
      (node (ref "DDR1") (pin "183") (pinfunction "183_183") (pintype "passive"))
      (node (ref "U1") (pin "132") (pinfunction "PG15_132") (pintype "passive"))
    )
    (net (code "104") (name "/RESET") (class "Default")
      (node (ref "C1") (pin "1") (pinfunction "1_1") (pintype "passive"))
      (node (ref "DDR1") (pin "138") (pinfunction "138_138") (pintype "passive"))
      (node (ref "JP1") (pin "4") (pinfunction "4_4") (pintype "passive"))
      (node (ref "R1") (pin "1") (pinfunction "1_1") (pintype "passive"))
      (node (ref "S1") (pin "1") (pinfunction "1_1") (pintype "passive"))
      (node (ref "U1") (pin "25") (pinfunction "NRST_25") (pintype "passive"))
    )
    (net (code "105") (name "/RTC_BAT") (class "Default")
      (node (ref "DDR1") (pin "164") (pinfunction "164_164") (pintype "passive"))
      (node (ref "U1") (pin "6") (pinfunction "VBAT_6") (pintype "passive"))
    )
    (net (code "106") (name "/SPI2_MISO") (class "Default")
      (node (ref "U1") (pin "75") (pinfunction "PB14/SPI2_MISO/USART3_RTS/TIM1_CH2N_75") (pintype "passive"))
      (node (ref "U2") (pin "2") (pinfunction "DO_2") (pintype "passive"))
    )
    (net (code "107") (name "/SPI2_MOSI") (class "Default")
      (node (ref "U1") (pin "76") (pinfunction "PB15/SPI2_MOSI/I2S2_SD/TIM1_CH3N_76") (pintype "passive"))
      (node (ref "U2") (pin "5") (pinfunction "DI_5") (pintype "passive"))
    )
    (net (code "108") (name "/SPI2_SCK") (class "Default")
      (node (ref "U1") (pin "74") (pinfunction "PB13/SPI2_SCK/I2S2_CK/USART3_CTS/TIM1_CH1N_74") (pintype "passive"))
      (node (ref "U2") (pin "6") (pinfunction "CLK_6") (pintype "passive"))
    )
    (net (code "109") (name "/T_CS") (class "Default")
      (node (ref "DDR1") (pin "117") (pinfunction "117_117") (pintype "passive"))
      (node (ref "U1") (pin "49") (pinfunction "PF11/FSMC_NIOS16_49") (pintype "passive"))
    )
    (net (code "110") (name "/T_MISO") (class "Default")
      (node (ref "DDR1") (pin "115") (pinfunction "115_115") (pintype "passive"))
      (node (ref "U1") (pin "48") (pinfunction "PB2/BOOT1_48") (pintype "passive"))
    )
    (net (code "111") (name "/T_MOSI") (class "Default")
      (node (ref "DDR1") (pin "142") (pinfunction "142_142") (pintype "passive"))
      (node (ref "U1") (pin "21") (pinfunction "PF9/ADC3_IN7/FSMC_CD_21") (pintype "passive"))
    )
    (net (code "112") (name "/T_PEN") (class "Default")
      (node (ref "DDR1") (pin "140") (pinfunction "140_140") (pintype "passive"))
      (node (ref "U1") (pin "22") (pinfunction "PF10/ADC3_IN8/FSMC_INTR_22") (pintype "passive"))
    )
    (net (code "113") (name "/T_SCK") (class "Default")
      (node (ref "DDR1") (pin "113") (pinfunction "113_113") (pintype "passive"))
      (node (ref "U1") (pin "47") (pinfunction "PB1/ADC12_IN9/TIM3_CH4/TIM8_CH3N_47") (pintype "passive"))
    )
    (net (code "114") (name "3V3") (class "Default")
      (node (ref "C10") (pin "2") (pinfunction "2_2") (pintype "passive"))
      (node (ref "C11") (pin "2") (pinfunction "2_2") (pintype "passive"))
      (node (ref "C12") (pin "2") (pinfunction "2_2") (pintype "passive"))
      (node (ref "C13") (pin "2") (pinfunction "2_2") (pintype "passive"))
      (node (ref "C14") (pin "2") (pinfunction "2_2") (pintype "passive"))
      (node (ref "C15") (pin "2") (pinfunction "2_2") (pintype "passive"))
      (node (ref "C16") (pin "2") (pinfunction "2_2") (pintype "passive"))
      (node (ref "C17") (pin "2") (pinfunction "2_2") (pintype "passive"))
      (node (ref "C18") (pin "2") (pinfunction "2_2") (pintype "passive"))
      (node (ref "C19") (pin "2") (pinfunction "2_2") (pintype "passive"))
      (node (ref "C2") (pin "1") (pinfunction "1_1") (pintype "passive"))
      (node (ref "C9") (pin "2") (pinfunction "2_2") (pintype "passive"))
      (node (ref "DDR1") (pin "37") (pinfunction "37_37") (pintype "passive"))
      (node (ref "DDR1") (pin "38") (pinfunction "38_38") (pintype "passive"))
      (node (ref "DDR1") (pin "39") (pinfunction "39_39") (pintype "passive"))
      (node (ref "DDR1") (pin "40") (pinfunction "40_40") (pintype "passive"))
      (node (ref "DDR1") (pin "41") (pinfunction "41_41") (pintype "passive"))
      (node (ref "DDR1") (pin "42") (pinfunction "42_42") (pintype "passive"))
      (node (ref "DDR1") (pin "43") (pinfunction "43_43") (pintype "passive"))
      (node (ref "DDR1") (pin "44") (pinfunction "44_44") (pintype "passive"))
      (node (ref "DDR1") (pin "45") (pinfunction "45_45") (pintype "passive"))
      (node (ref "DDR1") (pin "46") (pinfunction "46_46") (pintype "passive"))
      (node (ref "DDR1") (pin "47") (pinfunction "47_47") (pintype "passive"))
      (node (ref "DDR1") (pin "48") (pinfunction "48_48") (pintype "passive"))
      (node (ref "DDR1") (pin "49") (pinfunction "49_49") (pintype "passive"))
      (node (ref "DDR1") (pin "50") (pinfunction "50_50") (pintype "passive"))
      (node (ref "DDR1") (pin "51") (pinfunction "51_51") (pintype "passive"))
      (node (ref "DDR1") (pin "52") (pinfunction "52_52") (pintype "passive"))
      (node (ref "DDR1") (pin "53") (pinfunction "53_53") (pintype "passive"))
      (node (ref "DDR1") (pin "54") (pinfunction "54_54") (pintype "passive"))
      (node (ref "DDR1") (pin "55") (pinfunction "55_55") (pintype "passive"))
      (node (ref "DDR1") (pin "56") (pinfunction "56_56") (pintype "passive"))
      (node (ref "DDR1") (pin "57") (pinfunction "57_57") (pintype "passive"))
      (node (ref "DDR1") (pin "58") (pinfunction "58_58") (pintype "passive"))
      (node (ref "DDR1") (pin "59") (pinfunction "59_59") (pintype "passive"))
      (node (ref "DDR1") (pin "60") (pinfunction "60_60") (pintype "passive"))
      (node (ref "DDR1") (pin "61") (pinfunction "61_61") (pintype "passive"))
      (node (ref "DDR1") (pin "62") (pinfunction "62_62") (pintype "passive"))
      (node (ref "DDR1") (pin "63") (pinfunction "63_63") (pintype "passive"))
      (node (ref "DDR1") (pin "64") (pinfunction "64_64") (pintype "passive"))
      (node (ref "DDR1") (pin "65") (pinfunction "65_65") (pintype "passive"))
      (node (ref "DDR1") (pin "66") (pinfunction "66_66") (pintype "passive"))
      (node (ref "DDR1") (pin "67") (pinfunction "67_67") (pintype "passive"))
      (node (ref "DDR1") (pin "68") (pinfunction "68_68") (pintype "passive"))
      (node (ref "DDR1") (pin "69") (pinfunction "69_69") (pintype "passive"))
      (node (ref "DDR1") (pin "70") (pinfunction "70_70") (pintype "passive"))
      (node (ref "DDR1") (pin "71") (pinfunction "71_71") (pintype "passive"))
      (node (ref "DDR1") (pin "72") (pinfunction "72_72") (pintype "passive"))
      (node (ref "JP1") (pin "5") (pinfunction "5_5") (pintype "passive"))
      (node (ref "R1") (pin "2") (pinfunction "2_2") (pintype "passive"))
      (node (ref "R19") (pin "1") (pinfunction "1_1") (pintype "passive"))
      (node (ref "R5") (pin "2") (pinfunction "2_2") (pintype "passive"))
      (node (ref "U1") (pin "108") (pinfunction "VDD_108") (pintype "passive"))
      (node (ref "U1") (pin "121") (pinfunction "VDD_121") (pintype "passive"))
      (node (ref "U1") (pin "131") (pinfunction "VDD_131") (pintype "passive"))
      (node (ref "U1") (pin "144") (pinfunction "VDD_144") (pintype "passive"))
      (node (ref "U1") (pin "17") (pinfunction "VDD_17") (pintype "passive"))
      (node (ref "U1") (pin "39") (pinfunction "VDD_39") (pintype "passive"))
      (node (ref "U1") (pin "52") (pinfunction "VDD_52") (pintype "passive"))
      (node (ref "U1") (pin "62") (pinfunction "VDD_62") (pintype "passive"))
      (node (ref "U1") (pin "72") (pinfunction "VDD_72") (pintype "passive"))
      (node (ref "U1") (pin "84") (pinfunction "VDD_84") (pintype "passive"))
      (node (ref "U1") (pin "95") (pinfunction "VDD_95") (pintype "passive"))
      (node (ref "U2") (pin "3") (pinfunction "~{WP}_3") (pintype "passive"))
      (node (ref "U2") (pin "7") (pinfunction "~{HOLD}_ro_~{RESET}_7") (pintype "passive"))
      (node (ref "U2") (pin "8") (pinfunction "VCC_8") (pintype "passive"))
    )
    (net (code "115") (name "GND") (class "Default")
      (node (ref "C1") (pin "2") (pinfunction "2_2") (pintype "passive"))
      (node (ref "C10") (pin "1") (pinfunction "1_1") (pintype "passive"))
      (node (ref "C11") (pin "1") (pinfunction "1_1") (pintype "passive"))
      (node (ref "C12") (pin "1") (pinfunction "1_1") (pintype "passive"))
      (node (ref "C13") (pin "1") (pinfunction "1_1") (pintype "passive"))
      (node (ref "C14") (pin "1") (pinfunction "1_1") (pintype "passive"))
      (node (ref "C15") (pin "1") (pinfunction "1_1") (pintype "passive"))
      (node (ref "C16") (pin "1") (pinfunction "1_1") (pintype "passive"))
      (node (ref "C17") (pin "1") (pinfunction "1_1") (pintype "passive"))
      (node (ref "C18") (pin "1") (pinfunction "1_1") (pintype "passive"))
      (node (ref "C19") (pin "1") (pinfunction "1_1") (pintype "passive"))
      (node (ref "C2") (pin "2") (pinfunction "2_2") (pintype "passive"))
      (node (ref "C3") (pin "1") (pinfunction "1_1") (pintype "passive"))
      (node (ref "C4") (pin "1") (pinfunction "1_1") (pintype "passive"))
      (node (ref "C5") (pin "1") (pinfunction "1_1") (pintype "passive"))
      (node (ref "C6") (pin "1") (pinfunction "1_1") (pintype "passive"))
      (node (ref "C7") (pin "1") (pinfunction "1_1") (pintype "passive"))
      (node (ref "C8") (pin "1") (pinfunction "1_1") (pintype "passive"))
      (node (ref "C9") (pin "1") (pinfunction "1_1") (pintype "passive"))
      (node (ref "D4") (pin "K") (pinfunction "K_K") (pintype "passive"))
      (node (ref "DDR1") (pin "1") (pinfunction "1_1") (pintype "passive"))
      (node (ref "DDR1") (pin "10") (pinfunction "10_10") (pintype "passive"))
      (node (ref "DDR1") (pin "11") (pinfunction "11_11") (pintype "passive"))
      (node (ref "DDR1") (pin "12") (pinfunction "12_12") (pintype "passive"))
      (node (ref "DDR1") (pin "13") (pinfunction "13_13") (pintype "passive"))
      (node (ref "DDR1") (pin "14") (pinfunction "14_14") (pintype "passive"))
      (node (ref "DDR1") (pin "15") (pinfunction "15_15") (pintype "passive"))
      (node (ref "DDR1") (pin "16") (pinfunction "16_16") (pintype "passive"))
      (node (ref "DDR1") (pin "17") (pinfunction "17_17") (pintype "passive"))
      (node (ref "DDR1") (pin "18") (pinfunction "18_18") (pintype "passive"))
      (node (ref "DDR1") (pin "19") (pinfunction "19_19") (pintype "passive"))
      (node (ref "DDR1") (pin "2") (pinfunction "2_2") (pintype "passive"))
      (node (ref "DDR1") (pin "20") (pinfunction "20_20") (pintype "passive"))
      (node (ref "DDR1") (pin "21") (pinfunction "21_21") (pintype "passive"))
      (node (ref "DDR1") (pin "22") (pinfunction "22_22") (pintype "passive"))
      (node (ref "DDR1") (pin "23") (pinfunction "23_23") (pintype "passive"))
      (node (ref "DDR1") (pin "24") (pinfunction "24_24") (pintype "passive"))
      (node (ref "DDR1") (pin "25") (pinfunction "25_25") (pintype "passive"))
      (node (ref "DDR1") (pin "26") (pinfunction "26_26") (pintype "passive"))
      (node (ref "DDR1") (pin "27") (pinfunction "27_27") (pintype "passive"))
      (node (ref "DDR1") (pin "28") (pinfunction "28_28") (pintype "passive"))
      (node (ref "DDR1") (pin "29") (pinfunction "29_29") (pintype "passive"))
      (node (ref "DDR1") (pin "3") (pinfunction "3_3") (pintype "passive"))
      (node (ref "DDR1") (pin "30") (pinfunction "30_30") (pintype "passive"))
      (node (ref "DDR1") (pin "31") (pinfunction "31_31") (pintype "passive"))
      (node (ref "DDR1") (pin "32") (pinfunction "32_32") (pintype "passive"))
      (node (ref "DDR1") (pin "33") (pinfunction "33_33") (pintype "passive"))
      (node (ref "DDR1") (pin "34") (pinfunction "34_34") (pintype "passive"))
      (node (ref "DDR1") (pin "35") (pinfunction "35_35") (pintype "passive"))
      (node (ref "DDR1") (pin "36") (pinfunction "36_36") (pintype "passive"))
      (node (ref "DDR1") (pin "4") (pinfunction "4_4") (pintype "passive"))
      (node (ref "DDR1") (pin "5") (pinfunction "5_5") (pintype "passive"))
      (node (ref "DDR1") (pin "6") (pinfunction "6_6") (pintype "passive"))
      (node (ref "DDR1") (pin "7") (pinfunction "7_7") (pintype "passive"))
      (node (ref "DDR1") (pin "8") (pinfunction "8_8") (pintype "passive"))
      (node (ref "DDR1") (pin "9") (pinfunction "9_9") (pintype "passive"))
      (node (ref "JP1") (pin "1") (pinfunction "1_1") (pintype "passive"))
      (node (ref "R2") (pin "2") (pinfunction "2_2") (pintype "passive"))
      (node (ref "R3") (pin "2") (pinfunction "2_2") (pintype "passive"))
      (node (ref "S1") (pin "2") (pinfunction "2_2") (pintype "passive"))
      (node (ref "U1") (pin "107") (pinfunction "VSS_107") (pintype "passive"))
      (node (ref "U1") (pin "120") (pinfunction "VSS_120") (pintype "passive"))
      (node (ref "U1") (pin "130") (pinfunction "VSS_130") (pintype "passive"))
      (node (ref "U1") (pin "143") (pinfunction "VSS_143") (pintype "passive"))
      (node (ref "U1") (pin "16") (pinfunction "VSS_16") (pintype "passive"))
      (node (ref "U1") (pin "30") (pinfunction "VSSA_30") (pintype "passive"))
      (node (ref "U1") (pin "31") (pinfunction "Vref-_31") (pintype "passive"))
      (node (ref "U1") (pin "38") (pinfunction "VSS_38") (pintype "passive"))
      (node (ref "U1") (pin "51") (pinfunction "VSS_51") (pintype "passive"))
      (node (ref "U1") (pin "61") (pinfunction "VSS_61") (pintype "passive"))
      (node (ref "U1") (pin "71") (pinfunction "VSS_71") (pintype "passive"))
      (node (ref "U1") (pin "83") (pinfunction "VSS_83") (pintype "passive"))
      (node (ref "U1") (pin "94") (pinfunction "VSS_94") (pintype "passive"))
      (node (ref "U2") (pin "4") (pinfunction "GND_4") (pintype "passive"))
      (node (ref "Y2") (pin "2") (pinfunction "2_2") (pintype "passive"))
      (node (ref "Y2") (pin "4") (pinfunction "4_4") (pintype "passive"))
    )
    (net (code "116") (name "Net-(D1-PadK)") (class "Default")
      (node (ref "D1") (pin "K") (pinfunction "K_K") (pintype "passive"))
      (node (ref "R2") (pin "1") (pinfunction "1_1") (pintype "passive"))
    )
    (net (code "117") (name "Net-(D2-PadK)") (class "Default")
      (node (ref "D2") (pin "K") (pinfunction "K_K") (pintype "passive"))
      (node (ref "R3") (pin "1") (pinfunction "1_1") (pintype "passive"))
    )
    (net (code "118") (name "Net-(D4-PadA)") (class "Default")
      (node (ref "D4") (pin "A") (pinfunction "A_A") (pintype "passive"))
      (node (ref "R19") (pin "2") (pinfunction "2_2") (pintype "passive"))
    )
    (net (code "119") (name "Net-(U1-OSC_IN)") (class "Default")
      (node (ref "C5") (pin "2") (pinfunction "2_2") (pintype "passive"))
      (node (ref "R4") (pin "1") (pinfunction "1_1") (pintype "passive"))
      (node (ref "U1") (pin "23") (pinfunction "OSC_IN_23") (pintype "passive"))
      (node (ref "Y2") (pin "3") (pinfunction "3_3") (pintype "passive"))
    )
    (net (code "120") (name "Net-(U1-OSC_OUT)") (class "Default")
      (node (ref "C6") (pin "2") (pinfunction "2_2") (pintype "passive"))
      (node (ref "R4") (pin "2") (pinfunction "2_2") (pintype "passive"))
      (node (ref "U1") (pin "24") (pinfunction "OSC_OUT_24") (pintype "passive"))
      (node (ref "Y2") (pin "1") (pinfunction "1_1") (pintype "passive"))
    )
    (net (code "121") (name "Net-(U1-PC14-OSC32_IN)") (class "Default")
      (node (ref "C3") (pin "2") (pinfunction "2_2") (pintype "passive"))
      (node (ref "U1") (pin "8") (pinfunction "PC14-OSC32_IN_8") (pintype "passive"))
      (node (ref "Y1") (pin "1") (pinfunction "1_1") (pintype "passive"))
    )
    (net (code "122") (name "Net-(U1-PC15-OSC32_OUT)") (class "Default")
      (node (ref "C4") (pin "2") (pinfunction "2_2") (pintype "passive"))
      (node (ref "U1") (pin "9") (pinfunction "PC15-OSC32_OUT_9") (pintype "passive"))
      (node (ref "Y1") (pin "2") (pinfunction "2_2") (pintype "passive"))
    )
    (net (code "123") (name "Net-(U1-VDDA)") (class "Default")
      (node (ref "C7") (pin "2") (pinfunction "2_2") (pintype "passive"))
      (node (ref "C8") (pin "2") (pinfunction "2_2") (pintype "passive"))
      (node (ref "R5") (pin "1") (pinfunction "1_1") (pintype "passive"))
      (node (ref "U1") (pin "32") (pinfunction "Vref+_32") (pintype "passive"))
      (node (ref "U1") (pin "33") (pinfunction "VDDA_33") (pintype "passive"))
    )
    (net (code "124") (name "unconnected-(DDR1-Pad73)") (class "Default")
      (node (ref "DDR1") (pin "73") (pinfunction "73_73") (pintype "passive"))
    )
    (net (code "125") (name "unconnected-(DDR1-Pad74)") (class "Default")
      (node (ref "DDR1") (pin "74") (pinfunction "74_74") (pintype "passive"))
    )
    (net (code "126") (name "unconnected-(DDR1-Pad75)") (class "Default")
      (node (ref "DDR1") (pin "75") (pinfunction "75_75") (pintype "passive"))
    )
    (net (code "127") (name "unconnected-(DDR1-Pad76)") (class "Default")
      (node (ref "DDR1") (pin "76") (pinfunction "76_76") (pintype "passive"))
    )
    (net (code "128") (name "unconnected-(DDR1-Pad77)") (class "Default")
      (node (ref "DDR1") (pin "77") (pinfunction "77_77") (pintype "passive"))
    )
    (net (code "129") (name "unconnected-(DDR1-Pad78)") (class "Default")
      (node (ref "DDR1") (pin "78") (pinfunction "78_78") (pintype "passive"))
    )
    (net (code "130") (name "unconnected-(DDR1-Pad79)") (class "Default")
      (node (ref "DDR1") (pin "79") (pinfunction "79_79") (pintype "passive"))
    )
    (net (code "131") (name "unconnected-(DDR1-Pad80)") (class "Default")
      (node (ref "DDR1") (pin "80") (pinfunction "80_80") (pintype "passive"))
    )
    (net (code "132") (name "unconnected-(DDR1-Pad81)") (class "Default")
      (node (ref "DDR1") (pin "81") (pinfunction "81_81") (pintype "passive"))
    )
    (net (code "133") (name "unconnected-(DDR1-Pad82)") (class "Default")
      (node (ref "DDR1") (pin "82") (pinfunction "82_82") (pintype "passive"))
    )
    (net (code "134") (name "unconnected-(DDR1-Pad83)") (class "Default")
      (node (ref "DDR1") (pin "83") (pinfunction "83_83") (pintype "passive"))
    )
    (net (code "135") (name "unconnected-(DDR1-Pad84)") (class "Default")
      (node (ref "DDR1") (pin "84") (pinfunction "84_84") (pintype "passive"))
    )
    (net (code "136") (name "unconnected-(DDR1-Pad85)") (class "Default")
      (node (ref "DDR1") (pin "85") (pinfunction "85_85") (pintype "passive"))
    )
    (net (code "137") (name "unconnected-(DDR1-Pad86)") (class "Default")
      (node (ref "DDR1") (pin "86") (pinfunction "86_86") (pintype "passive"))
    )
    (net (code "138") (name "unconnected-(DDR1-Pad87)") (class "Default")
      (node (ref "DDR1") (pin "87") (pinfunction "87_87") (pintype "passive"))
    )
    (net (code "139") (name "unconnected-(DDR1-Pad88)") (class "Default")
      (node (ref "DDR1") (pin "88") (pinfunction "88_88") (pintype "passive"))
    )
    (net (code "140") (name "unconnected-(DDR1-Pad89)") (class "Default")
      (node (ref "DDR1") (pin "89") (pinfunction "89_89") (pintype "passive"))
    )
    (net (code "141") (name "unconnected-(DDR1-Pad90)") (class "Default")
      (node (ref "DDR1") (pin "90") (pinfunction "90_90") (pintype "passive"))
    )
    (net (code "142") (name "unconnected-(DDR1-Pad91)") (class "Default")
      (node (ref "DDR1") (pin "91") (pinfunction "91_91") (pintype "passive"))
    )
    (net (code "143") (name "unconnected-(DDR1-Pad92)") (class "Default")
      (node (ref "DDR1") (pin "92") (pinfunction "92_92") (pintype "passive"))
    )
    (net (code "144") (name "unconnected-(DDR1-Pad93)") (class "Default")
      (node (ref "DDR1") (pin "93") (pinfunction "93_93") (pintype "passive"))
    )
    (net (code "145") (name "unconnected-(DDR1-Pad94)") (class "Default")
      (node (ref "DDR1") (pin "94") (pinfunction "94_94") (pintype "passive"))
    )
    (net (code "146") (name "unconnected-(DDR1-Pad95)") (class "Default")
      (node (ref "DDR1") (pin "95") (pinfunction "95_95") (pintype "passive"))
    )
    (net (code "147") (name "unconnected-(DDR1-Pad96)") (class "Default")
      (node (ref "DDR1") (pin "96") (pinfunction "96_96") (pintype "passive"))
    )
    (net (code "148") (name "unconnected-(U1-NC-Pad106)") (class "Default")
      (node (ref "U1") (pin "106") (pinfunction "NC_106") (pintype "passive"))
    )
  )
)
